# H1FR0.net
KiCad netlist of a schematic drawn in EAGLE
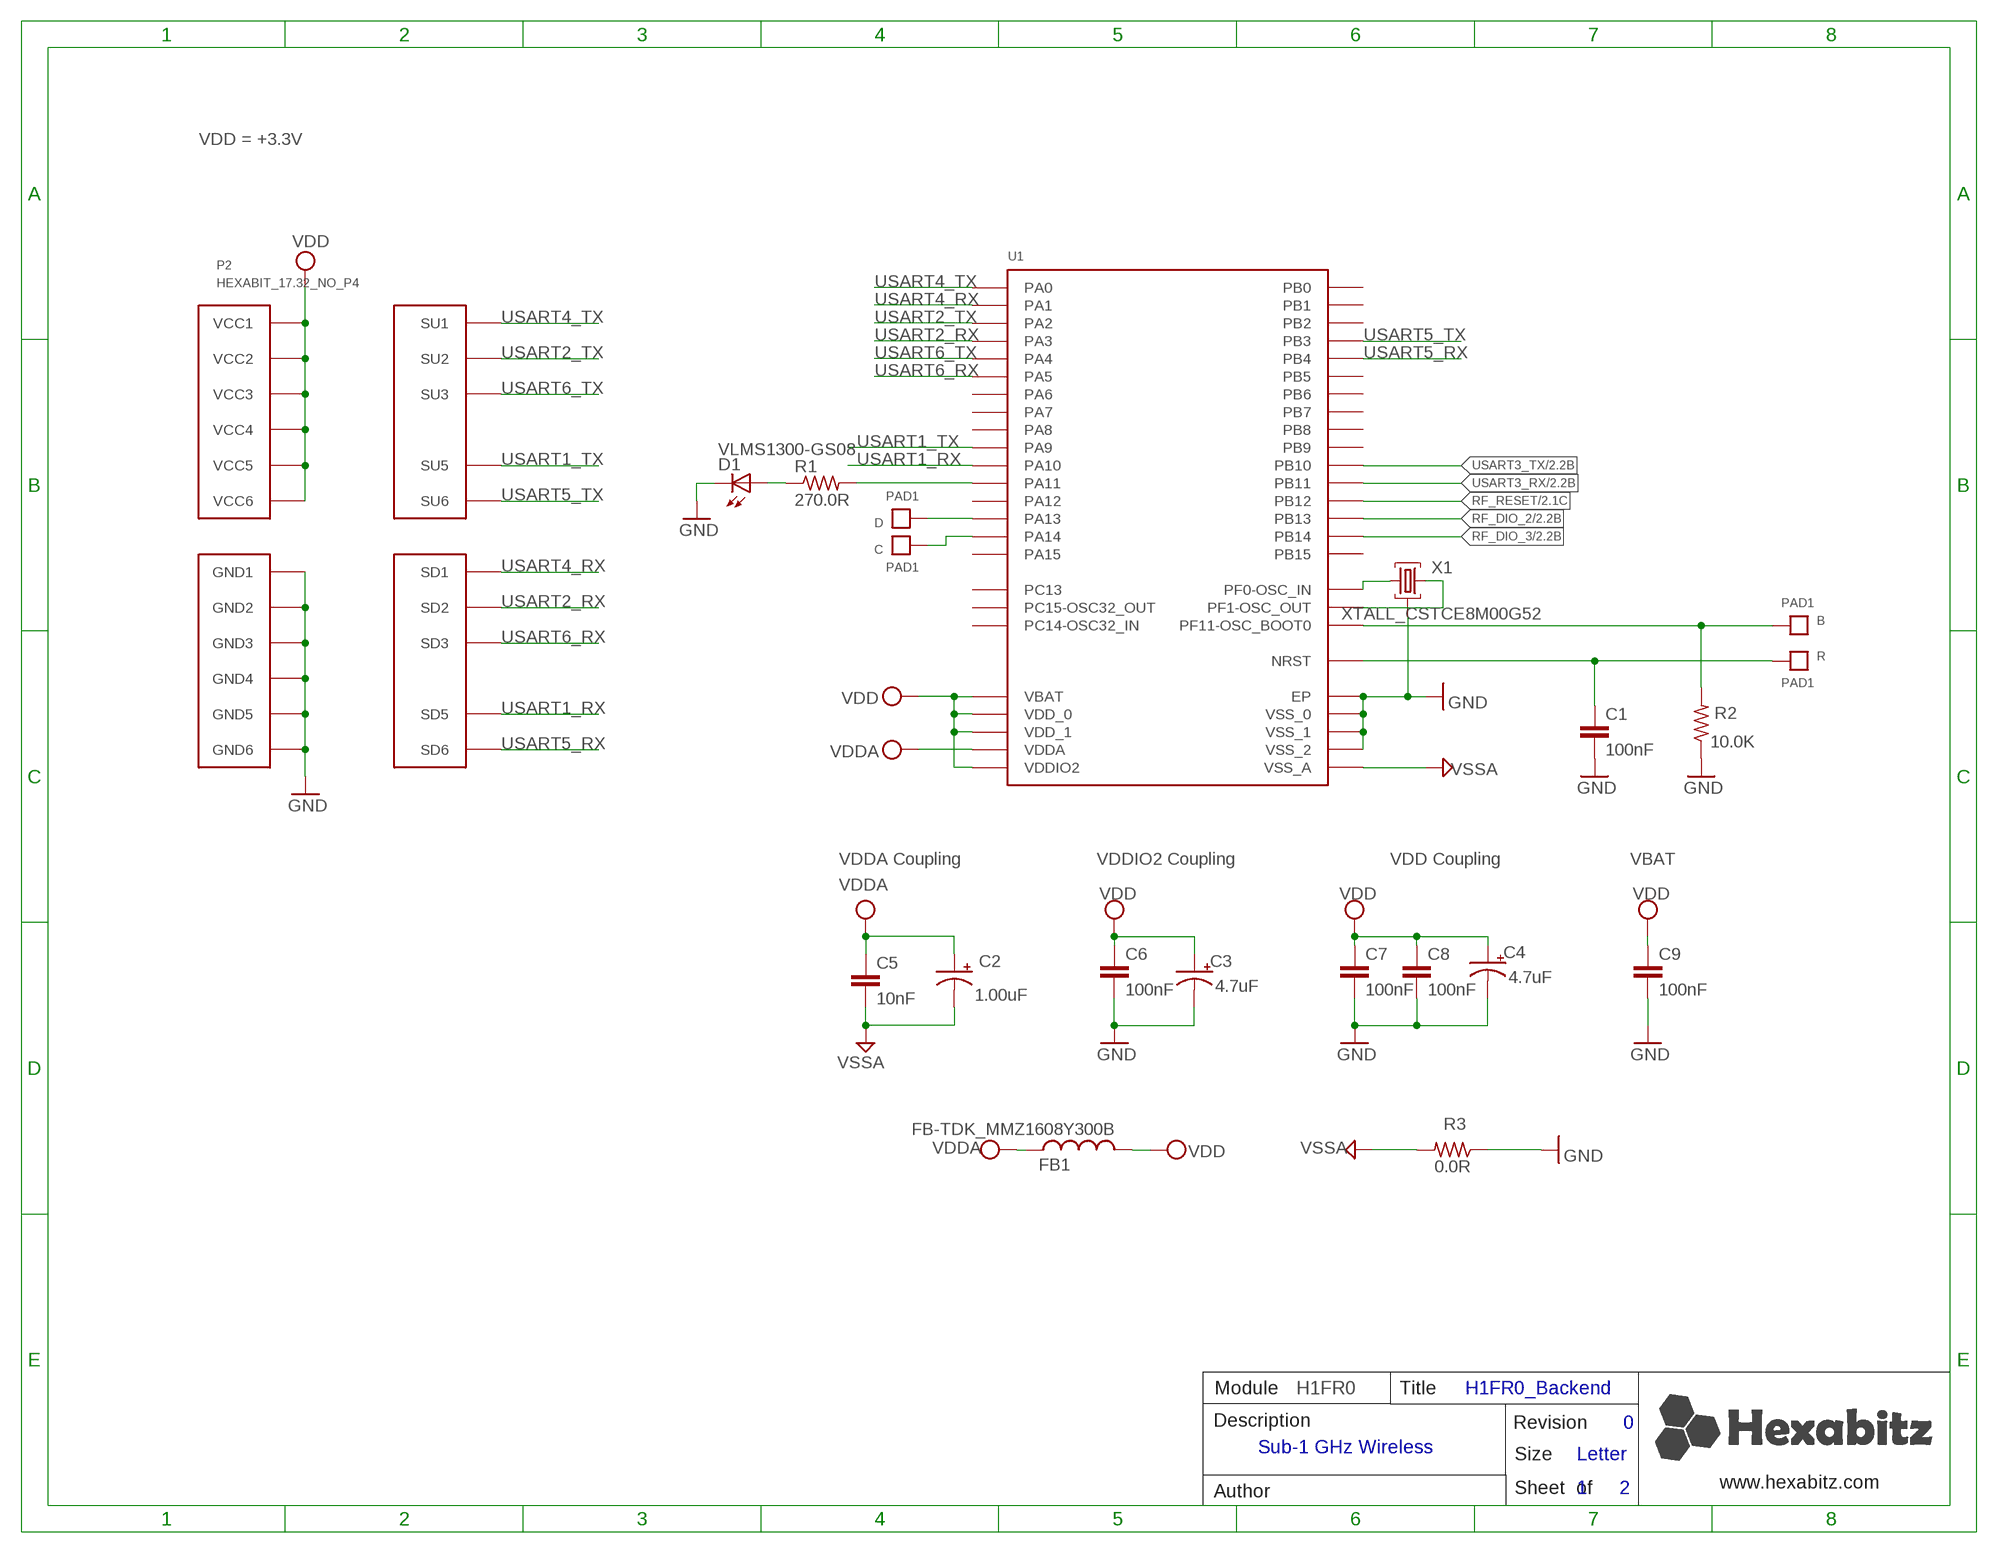
[diagram p0: schematic, sheet 1]
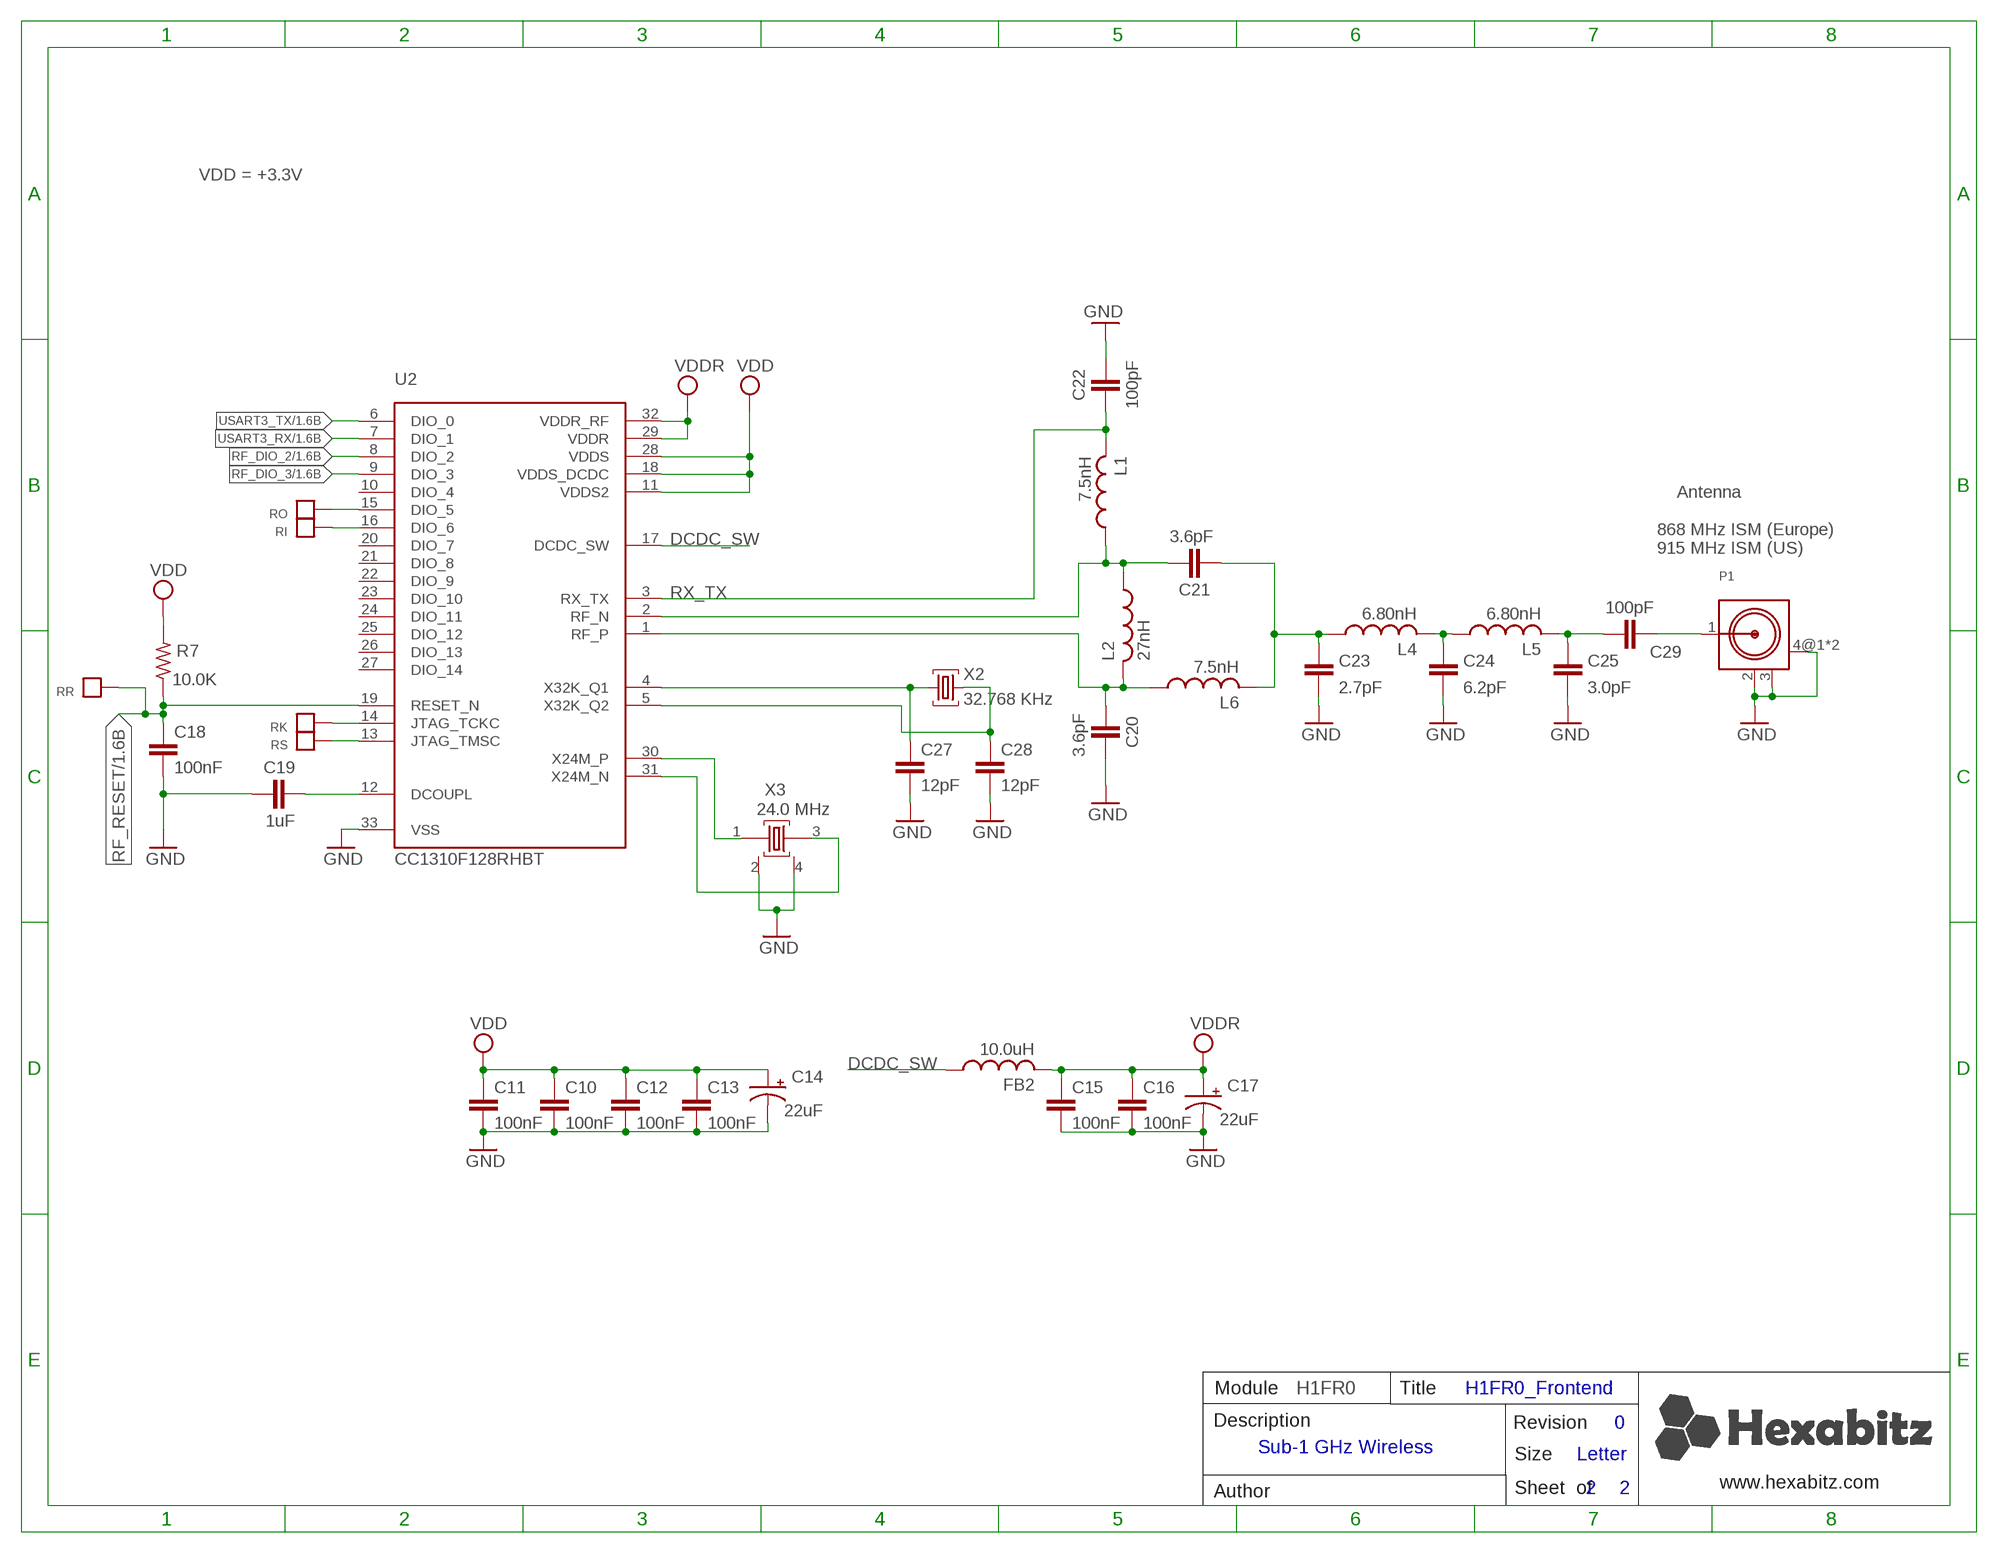
[diagram p1: schematic, sheet 2]

(export (version "E")
  (design (tool "Eeschema 10.0.6"))
  (components
    (comp (ref "C10")
      (value "100nF")
      (footprint "eagle-import:C-0402")
      (fields
        (field (name "MFN") "Murata")
        (field (name "MPN") "GRM155R70J104KA01D")
        (field (name "OCTOPART_URL") "https://octopart.com/grm155r70j104ka01d-murata-17930200")
        (field (name "TOLERANCE") "±10%")
        (field (name "VOLTAGE_RATING") "6.3 V")
      )
      (libsource (lib "eagle-import") (part "C-0402"))
    )
    (comp (ref "C11")
      (value "100nF")
      (footprint "eagle-import:C-0402")
      (fields
        (field (name "MFN") "Murata")
        (field (name "MPN") "GRM155R70J104KA01D")
        (field (name "OCTOPART_URL") "https://octopart.com/grm155r70j104ka01d-murata-17930200")
        (field (name "TOLERANCE") "±10%")
        (field (name "VOLTAGE_RATING") "6.3 V")
      )
      (libsource (lib "eagle-import") (part "C-0402"))
    )
    (comp (ref "C12")
      (value "100nF")
      (footprint "eagle-import:C-0402")
      (fields
        (field (name "MFN") "Murata")
        (field (name "MPN") "GRM155R70J104KA01D")
        (field (name "OCTOPART_URL") "https://octopart.com/grm155r70j104ka01d-murata-17930200")
        (field (name "TOLERANCE") "±10%")
        (field (name "VOLTAGE_RATING") "6.3 V")
      )
      (libsource (lib "eagle-import") (part "C-0402"))
    )
    (comp (ref "C13")
      (value "100nF")
      (footprint "eagle-import:C-0402")
      (fields
        (field (name "MFN") "Murata")
        (field (name "MPN") "GRM155R70J104KA01D")
        (field (name "OCTOPART_URL") "https://octopart.com/grm155r70j104ka01d-murata-17930200")
        (field (name "TOLERANCE") "±10%")
        (field (name "VOLTAGE_RATING") "6.3 V")
      )
      (libsource (lib "eagle-import") (part "C-0402"))
    )
    (comp (ref "C14")
      (value "22uF")
      (footprint "eagle-import:C-0805")
      (fields
        (field (name "CAPACITANCE") "22uF")
        (field (name "MFN") "Yageo")
        (field (name "MPN") "CC0805KKX5R5BB226")
        (field (name "OCTOPART_URL") "https://octopart.com/search?q=CC0805KKX5R5BB226&start=0")
        (field (name "TOLERANCE") "10%")
        (field (name "VOLTAGE_RATING") "6.3V")
      )
      (libsource (lib "eagle-import") (part "C-0805"))
    )
    (comp (ref "C15")
      (value "100nF")
      (footprint "eagle-import:C-0402")
      (fields
        (field (name "MFN") "Murata")
        (field (name "MPN") "GRM155R70J104KA01D")
        (field (name "OCTOPART_URL") "https://octopart.com/grm155r70j104ka01d-murata-17930200")
        (field (name "TOLERANCE") "±10%")
        (field (name "VOLTAGE_RATING") "6.3 V")
      )
      (libsource (lib "eagle-import") (part "C-0402"))
    )
    (comp (ref "C16")
      (value "100nF")
      (footprint "eagle-import:C-0402")
      (fields
        (field (name "MFN") "Murata")
        (field (name "MPN") "GRM155R70J104KA01D")
        (field (name "OCTOPART_URL") "https://octopart.com/grm155r70j104ka01d-murata-17930200")
        (field (name "TOLERANCE") "±10%")
        (field (name "VOLTAGE_RATING") "6.3 V")
      )
      (libsource (lib "eagle-import") (part "C-0402"))
    )
    (comp (ref "C17")
      (value "22uF")
      (footprint "eagle-import:C-0805")
      (fields
        (field (name "CAPACITANCE") "22uF")
        (field (name "MFN") "Yageo")
        (field (name "MPN") "CC0805KKX5R5BB226")
        (field (name "OCTOPART_URL") "https://octopart.com/search?q=CC0805KKX5R5BB226&start=0")
        (field (name "TOLERANCE") "10%")
        (field (name "VOLTAGE_RATING") "6.3V")
      )
      (libsource (lib "eagle-import") (part "C-0805"))
    )
    (comp (ref "C18")
      (value "100nF")
      (footprint "eagle-import:C-0402")
      (fields
        (field (name "MFN") "Murata")
        (field (name "MPN") "GRM155R70J104KA01D")
        (field (name "OCTOPART_URL") "https://octopart.com/grm155r70j104ka01d-murata-17930200")
        (field (name "TOLERANCE") "±10%")
        (field (name "VOLTAGE_RATING") "6.3 V")
      )
      (libsource (lib "eagle-import") (part "C-0402"))
    )
    (comp (ref "C19")
      (value "1uF")
      (footprint "eagle-import:C-0603")
      (fields
        (field (name "CAPACITANCE") "1uF")
        (field (name "MFN") "Murata")
        (field (name "MPN") "GRM188R70J105KA01D")
        (field (name "OCTOPART_URL") "https://octopart.com/grm188r70j105ka01d-murata-197450")
        (field (name "TOLERANCE") "10%")
        (field (name "VOLTAGE_RATING") "6.3V")
      )
      (libsource (lib "eagle-import") (part "C-0603"))
    )
    (comp (ref "C20")
      (value "3.6pF")
      (footprint "eagle-import:C-0402")
      (fields
        (field (name "MFN") "Murata")
        (field (name "MPN") "GRM1555C1H3R6CA01D")
        (field (name "OCTOPART_URL") "https://octopart.com/grm1555c1h3r6ca01d-murata-18814425")
        (field (name "TOLERANCE") "±0.25pF")
        (field (name "VOLTAGE_RATING") "50 V")
      )
      (libsource (lib "eagle-import") (part "C-0402"))
    )
    (comp (ref "C21")
      (value "3.6pF")
      (footprint "eagle-import:C-0402")
      (fields
        (field (name "MFN") "Murata")
        (field (name "MPN") "GRM1555C1H3R6CA01D")
        (field (name "OCTOPART_URL") "https://octopart.com/grm1555c1h3r6ca01d-murata-18814425")
        (field (name "TOLERANCE") "±0.25%")
        (field (name "VOLTAGE_RATING") "50 V")
      )
      (libsource (lib "eagle-import") (part "C-0402"))
    )
    (comp (ref "C22")
      (value "100pF")
      (footprint "eagle-import:C-0402")
      (fields
        (field (name "MFN") "Murata")
        (field (name "MPN") "GRM1555C1H101JA01D")
        (field (name "OCTOPART_URL") "https://octopart.com/grm1555c1h101ja01d-murata-15197512")
        (field (name "TOLERANCE") "±5%")
        (field (name "VOLTAGE_RATING") "50V")
      )
      (libsource (lib "eagle-import") (part "C-0402"))
    )
    (comp (ref "C23")
      (value "2.7pF")
      (footprint "eagle-import:C-0402")
      (fields
        (field (name "MFN") "Murata")
        (field (name "MPN") "GRM1555C1H2R7CA01D")
        (field (name "OCTOPART_URL") "https://octopart.com/search?q=GRM1555C1H2R7CA01D&start=0")
        (field (name "TOLERANCE") "±0.25 pF")
        (field (name "VOLTAGE_RATING") "50 V")
      )
      (libsource (lib "eagle-import") (part "C-0402"))
    )
    (comp (ref "C24")
      (value "6.2pF")
      (footprint "eagle-import:C-0402")
      (fields
        (field (name "MFN") "Murata")
        (field (name "MPN") "GRM1555C1H6R2CA01D")
        (field (name "OCTOPART_URL") "https://octopart.com/search?q=GRM1555C1H6R2CA01D&start=0")
        (field (name "TOLERANCE") "±0.25pF")
        (field (name "VOLTAGE_RATING") "50 V")
      )
      (libsource (lib "eagle-import") (part "C-0402"))
    )
    (comp (ref "C25")
      (value "3.0pF")
      (footprint "eagle-import:C-0402")
      (fields
        (field (name "MFN") "Murata")
        (field (name "MPN") "GRM1555C1H3R0CA01D")
        (field (name "OCTOPART_URL") "https://octopart.com/search?q=GRM1555C1H3R0CA01D&start=0")
        (field (name "TOLERANCE") "±0.25 pF")
        (field (name "VOLTAGE_RATING") "50 V")
      )
      (libsource (lib "eagle-import") (part "C-0402"))
    )
    (comp (ref "C27")
      (value "12pF")
      (footprint "eagle-import:C-0603")
      (fields
        (field (name "CAPACITANCE") "12pF")
        (field (name "MFN") "AVX")
        (field (name "MPN") "06035A120JAT2A")
        (field (name "OCTOPART_URL") "https://octopart.com/06035a120jat2a-avx-194785")
        (field (name "TOLERANCE") "5%")
        (field (name "VOLTAGE_RATING") "50V")
      )
      (libsource (lib "eagle-import") (part "C-0603"))
    )
    (comp (ref "C28")
      (value "12pF")
      (footprint "eagle-import:C-0603")
      (fields
        (field (name "CAPACITANCE") "12pF")
        (field (name "MFN") "AVX")
        (field (name "MPN") "06035A120JAT2A")
        (field (name "OCTOPART_URL") "https://octopart.com/06035a120jat2a-avx-194785")
        (field (name "TOLERANCE") "5%")
        (field (name "VOLTAGE_RATING") "50V")
      )
      (libsource (lib "eagle-import") (part "C-0603"))
    )
    (comp (ref "C29")
      (value "100pF")
      (footprint "eagle-import:C-0402")
      (fields
        (field (name "MFN") "Murata")
        (field (name "MPN") "GRM1555C1H101JA01D")
        (field (name "OCTOPART_URL") "https://octopart.com/grm1555c1h101ja01d-murata-15197512")
        (field (name "TOLERANCE") "±5%")
        (field (name "VOLTAGE_RATING") "50V")
      )
      (libsource (lib "eagle-import") (part "C-0402"))
    )
    (comp (ref "FB2")
      (value "10.0uH")
      (footprint "eagle-import:FB-0805")
      (fields
        (field (name "MFN") "Taiyo Yuden")
        (field (name "MPN") "CKS2125100M-T")
        (field (name "OCTOPART_URL") "http://octopart.com/cks2125100m-t-taiyo+yuden-18605517")
      )
      (libsource (lib "eagle-import") (part "FB-0805"))
    )
    (comp (ref "L1")
      (value "7.5nH")
      (footprint "eagle-import:IND-0402")
      (fields
        (field (name "INDUCTANCE") "7.5nH")
        (field (name "MFN") "Murata")
        (field (name "MPN") "LQG15HS7N5J02D")
        (field (name "OCTOPART_URL") "https://octopart.com/search?q=LQG15HS7N5J02D&start=0")
      )
      (libsource (lib "eagle-import") (part "IND-0402"))
    )
    (comp (ref "L2")
      (value "27nH")
      (footprint "eagle-import:IND-0402")
      (fields
        (field (name "INDUCTANCE") "27nH")
        (field (name "MFN") "Murata")
        (field (name "MPN") "LQG15HS27NJ02D")
        (field (name "OCTOPART_URL") "https://octopart.com/search?q=LQG15HS27NJ02D&start=0")
      )
      (libsource (lib "eagle-import") (part "IND-0402"))
    )
    (comp (ref "L4")
      (value "6.80nH")
      (footprint "eagle-import:IND-0402")
      (fields
        (field (name "INDUCTANCE") "6.80nH")
        (field (name "MFN") "Murata")
        (field (name "MPN") "LQW15AN6N8G00D")
        (field (name "OCTOPART_URL") "https://octopart.com/lqw15an6n8g00d-murata-7896134")
      )
      (libsource (lib "eagle-import") (part "IND-0402"))
    )
    (comp (ref "L5")
      (value "6.80nH")
      (footprint "eagle-import:IND-0402")
      (fields
        (field (name "INDUCTANCE") "6.80nH")
        (field (name "MFN") "Murata")
        (field (name "MPN") "LQW15AN6N8G00D")
        (field (name "OCTOPART_URL") "https://octopart.com/lqw15an6n8g00d-murata-7896134")
      )
      (libsource (lib "eagle-import") (part "IND-0402"))
    )
    (comp (ref "L6")
      (value "7.5nH")
      (footprint "eagle-import:IND-0402")
      (fields
        (field (name "INDUCTANCE") "7.5nH")
        (field (name "MFN") "Murata")
        (field (name "MPN") "LQG15HS7N5J02D")
        (field (name "OCTOPART_URL") "https://octopart.com/search?q=LQG15HS7N5J02D&start=0")
      )
      (libsource (lib "eagle-import") (part "IND-0402"))
    )
    (comp (ref "P1")
      (value "5-1814400-1")
      (footprint "eagle-import:5-1814400-1")
      (libsource (lib "eagle-import") (part "5-1814400-1"))
    )
    (comp (ref "R7")
      (value "10.0K")
      (footprint "eagle-import:R-0603")
      (fields
        (field (name "MFN") "Yageo")
        (field (name "MPN") "RC0603JR-0710KL")
        (field (name "OCTOPART_URL") "https://octopart.com/search?q=RC0603JR-0710KL&start=0")
        (field (name "RESISTANCE") "10.0K Ohm")
        (field (name "TOLERANCE") "5%")
      )
      (libsource (lib "eagle-import") (part "R-0603"))
    )
    (comp (ref "RI")
      (value "PAD4")
      (footprint "eagle-import:PAD4")
      (libsource (lib "eagle-import") (part "PAD4"))
    )
    (comp (ref "RK")
      (value "PAD4")
      (footprint "eagle-import:PAD4")
      (libsource (lib "eagle-import") (part "PAD4"))
    )
    (comp (ref "RO")
      (value "PAD4")
      (footprint "eagle-import:PAD4")
      (libsource (lib "eagle-import") (part "PAD4"))
    )
    (comp (ref "RR")
      (value "PAD4")
      (footprint "eagle-import:PAD4")
      (libsource (lib "eagle-import") (part "PAD4"))
    )
    (comp (ref "RS")
      (value "PAD4")
      (footprint "eagle-import:PAD4")
      (libsource (lib "eagle-import") (part "PAD4"))
    )
    (comp (ref "U2")
      (value "CC1310F128RHBT")
      (footprint "eagle-import:CC1310F128RHBT")
      (libsource (lib "eagle-import") (part "CC1310F128RHBT"))
    )
    (comp (ref "X2")
      (value "32.768 KHz")
      (footprint "eagle-import:XTALL_FC-12M")
      (fields (field (name "MPN") "FC-12M 32.7680KA-A3"))
      (libsource (lib "eagle-import") (part "XTALL_FC-12M"))
    )
    (comp (ref "X3")
      (value "24.0 MHz")
      (footprint "eagle-import:XTALL_TXS-3225-24.0000M")
      (fields (field (name "MPN") "TSX-3225 24.0000MF20G-AC3"))
      (libsource (lib "eagle-import") (part "XTALL_TXS-3225-24.0000M"))
    )
    (comp (ref "B")
      (value "PAD1")
      (footprint "eagle-import:PAD1")
      (libsource (lib "eagle-import") (part "PAD1"))
    )
    (comp (ref "C")
      (value "PAD1")
      (footprint "eagle-import:PAD1")
      (libsource (lib "eagle-import") (part "PAD1"))
    )
    (comp (ref "C1")
      (value "100nF")
      (footprint "eagle-import:C-0603")
      (fields
        (field (name "CAPACITANCE") "100nF")
        (field (name "MFN") "KEMET")
        (field (name "MPN") "C0603C104K8RACTU")
        (field (name "OCTOPART_URL") "https://octopart.com/c0603c104k8ractu-kemet-145075?r=sp&s=9bS9ASSwSEqMCE9KBEQZ0g")
        (field (name "TOLERANCE") "10%")
        (field (name "VOLTAGE_RATING") "10V")
      )
      (libsource (lib "eagle-import") (part "C-0603"))
    )
    (comp (ref "C2")
      (value "1.00uF")
      (footprint "eagle-import:C-0805")
      (fields
        (field (name "CAPACITANCE") "1.00uF")
        (field (name "MFN") "Yageo")
        (field (name "MPN") "CC0805KKX7R7BB105")
        (field (name "OCTOPART_URL") "https://octopart.com/cc0805kkx7r7bb105-yageo-8376555?r=sp&s=YKl1wwtkROau_X5nniH2ig")
        (field (name "TOLERANCE") "10%")
        (field (name "VOLTAGE_RATING") "16V")
      )
      (libsource (lib "eagle-import") (part "C-0805"))
    )
    (comp (ref "C3")
      (value "4.7uF")
      (footprint "eagle-import:C-0805")
      (fields
        (field (name "CAPACITANCE") "4.7uF")
        (field (name "MFN") "Murata")
        (field (name "MPN") "GRM21BC81E475KA12L")
        (field (name "OCTOPART_URL") "https://octopart.com/grm21bc81e475ka12l-murata-10331911?r=sp&s=RY3qZSD8T6mG6TC9CHI5qQ")
        (field (name "TOLERANCE") "10%")
        (field (name "VOLTAGE_RATING") "25V")
      )
      (libsource (lib "eagle-import") (part "C-0805"))
    )
    (comp (ref "C4")
      (value "4.7uF")
      (footprint "eagle-import:C-0805")
      (fields
        (field (name "CAPACITANCE") "4.7uF")
        (field (name "MFN") "Murata")
        (field (name "MPN") "GRM21BC81E475KA12L")
        (field (name "OCTOPART_URL") "https://octopart.com/grm21bc81e475ka12l-murata-10331911?r=sp&s=RY3qZSD8T6mG6TC9CHI5qQ")
        (field (name "TOLERANCE") "10%")
        (field (name "VOLTAGE_RATING") "25V")
      )
      (libsource (lib "eagle-import") (part "C-0805"))
    )
    (comp (ref "C5")
      (value "10nF")
      (footprint "eagle-import:C-0603")
      (fields
        (field (name "CAPACITANCE") "10nF")
        (field (name "MFN") "KEMET")
        (field (name "MPN") "C0603C103K5RACTU")
        (field (name "OCTOPART_URL") "https://octopart.com/c0603c103k5ractu-kemet-133094?r=sp&s=R_iPBxLnSmGqhkU2rIMFpg")
        (field (name "TOLERANCE") "10%")
        (field (name "VOLTAGE_RATING") "50V")
      )
      (libsource (lib "eagle-import") (part "C-0603"))
    )
    (comp (ref "C6")
      (value "100nF")
      (footprint "eagle-import:C-0603")
      (fields
        (field (name "CAPACITANCE") "100nF")
        (field (name "MFN") "KEMET")
        (field (name "MPN") "C0603C104K8RACTU")
        (field (name "OCTOPART_URL") "https://octopart.com/c0603c104k8ractu-kemet-145075?r=sp&s=9bS9ASSwSEqMCE9KBEQZ0g")
        (field (name "TOLERANCE") "10%")
        (field (name "VOLTAGE_RATING") "10V")
      )
      (libsource (lib "eagle-import") (part "C-0603"))
    )
    (comp (ref "C7")
      (value "100nF")
      (footprint "eagle-import:C-0603")
      (fields
        (field (name "CAPACITANCE") "100nF")
        (field (name "MFN") "KEMET")
        (field (name "MPN") "C0603C104K8RACTU")
        (field (name "OCTOPART_URL") "https://octopart.com/c0603c104k8ractu-kemet-145075?r=sp&s=9bS9ASSwSEqMCE9KBEQZ0g")
        (field (name "TOLERANCE") "10%")
        (field (name "VOLTAGE_RATING") "10")
      )
      (libsource (lib "eagle-import") (part "C-0603"))
    )
    (comp (ref "C8")
      (value "100nF")
      (footprint "eagle-import:C-0603")
      (fields
        (field (name "CAPACITANCE") "100nF")
        (field (name "MFN") "KEMET")
        (field (name "MPN") "C0603C104K8RACTU")
        (field (name "OCTOPART_URL") "https://octopart.com/c0603c104k8ractu-kemet-145075?r=sp&s=9bS9ASSwSEqMCE9KBEQZ0g")
        (field (name "TOLERANCE") "10%")
        (field (name "VOLTAGE_RATING") "10V")
      )
      (libsource (lib "eagle-import") (part "C-0603"))
    )
    (comp (ref "C9")
      (value "100nF")
      (footprint "eagle-import:C-0603")
      (fields
        (field (name "CAPACITANCE") "100nF")
        (field (name "MFN") "KEMET")
        (field (name "MPN") "C0603C104K8RACTU")
        (field (name "OCTOPART_URL") "https://octopart.com/c0603c104k8ractu-kemet-145075?r=sp&s=9bS9ASSwSEqMCE9KBEQZ0g")
        (field (name "TOLERANCE") "10V")
        (field (name "VOLTAGE_RATING") "10%")
      )
      (libsource (lib "eagle-import") (part "C-0603"))
    )
    (comp (ref "D")
      (value "PAD1")
      (footprint "eagle-import:PAD1")
      (libsource (lib "eagle-import") (part "PAD1"))
    )
    (comp (ref "D1")
      (value "VLMS1300-GS08")
      (footprint "eagle-import:VLMS1300-GS08")
      (fields
        (field (name "MFN") "Vishay")
        (field (name "MPN") "VLMS1300-GS08")
        (field (name "OCTOPART_URL") "https://octopart.com/vlms1300-gs08-vishay-21709201?r=sp&s=_gcP4_q8T1SC6PJQPTQ9yA")
      )
      (libsource (lib "eagle-import") (part "VLMS1300-GS08"))
    )
    (comp (ref "FB1")
      (value "FB-TDK_MMZ1608Y300B")
      (footprint "eagle-import:FB-TDK_MMZ1608Y300B")
      (fields
        (field (name "MFN") "TDK ")
        (field (name "MPN") "MMZ1608Y300B")
        (field (name "OCTOPART_URL") "https://octopart.com/mmz1608y300b-tdk-368280?r=sp&s=cd9_2ZEqQ9q9UNBuQgHAiA")
      )
      (libsource (lib "eagle-import") (part "FB-TDK_MMZ1608Y300B"))
    )
    (comp (ref "P2")
      (value "HEXABIT_17.32_NO_P4")
      (footprint "eagle-import:HEXABIT_17.32_NO_P4")
      (libsource (lib "eagle-import") (part "HEXABIT_17.32_NO_P4"))
    )
    (comp (ref "R")
      (value "PAD1")
      (footprint "eagle-import:PAD1")
      (libsource (lib "eagle-import") (part "PAD1"))
    )
    (comp (ref "R1")
      (value "270.0R")
      (footprint "eagle-import:R-0603")
      (fields
        (field (name "MFN") "Yageo")
        (field (name "MPN") "RC0603FR-07270RL")
        (field (name "OCTOPART_URL") "https://octopart.com/search?q=RC0603FR-07270RL&start=0")
        (field (name "RESISTANCE") "270.0 Ohm")
        (field (name "TOLERANCE") "1%")
      )
      (libsource (lib "eagle-import") (part "R-0603"))
    )
    (comp (ref "R2")
      (value "10.0K")
      (footprint "eagle-import:R-0603")
      (fields
        (field (name "MFN") "Yageo")
        (field (name "MPN") "RC0603JR-0710KL")
        (field (name "OCTOPART_URL") "https://octopart.com/search?q=RC0603JR-0710KL&start=0")
        (field (name "RESISTANCE") "10.0K Ohm")
        (field (name "TOLERANCE") "5%")
      )
      (libsource (lib "eagle-import") (part "R-0603"))
    )
    (comp (ref "R3")
      (value "0.0R")
      (footprint "eagle-import:R-0603")
      (fields
        (field (name "MFN") "Yageo")
        (field (name "MPN") "RC0603JR-070RL")
        (field (name "OCTOPART_URL") "https://octopart.com/rc0603jr-070rl-yageo-1241539?r=sp&s=X2NteqRjRNWrnx42Y0aliA")
        (field (name "RESISTANCE") "0.0 Ohm")
      )
      (libsource (lib "eagle-import") (part "R-0603"))
    )
    (comp (ref "U1")
      (value "STM32F091CBU6")
      (footprint "eagle-import:STM32F091CBU6")
      (libsource (lib "eagle-import") (part "STM32F091CBU6"))
    )
    (comp (ref "X1")
      (value "XTALL_CSTCE8M00G52")
      (footprint "eagle-import:XTALL_CSTCE8M00G52")
      (fields (field (name "MPN") "CSTCE8M00G52Z-R0"))
      (libsource (lib "eagle-import") (part "XTALL_CSTCE8M00G52"))
    )
  )
  (nets
    (net (code "1") (name "DCDC_SW") (class "Default")
      (node (ref "FB2") (pin "1") (pinfunction "1_1") (pintype "passive"))
      (node (ref "U2") (pin "17") (pinfunction "DCDC_SW_17") (pintype "bidirectional"))
    )
    (net (code "2") (name "GND") (class "Default")
      (node (ref "C1") (pin "2") (pinfunction "2_2") (pintype "passive"))
      (node (ref "C10") (pin "2") (pinfunction "2_2") (pintype "passive"))
      (node (ref "C11") (pin "2") (pinfunction "2_2") (pintype "passive"))
      (node (ref "C12") (pin "2") (pinfunction "2_2") (pintype "passive"))
      (node (ref "C13") (pin "2") (pinfunction "2_2") (pintype "passive"))
      (node (ref "C14") (pin "2") (pinfunction "-_2") (pintype "passive"))
      (node (ref "C15") (pin "2") (pinfunction "2_2") (pintype "passive"))
      (node (ref "C16") (pin "2") (pinfunction "2_2") (pintype "passive"))
      (node (ref "C17") (pin "2") (pinfunction "-_2") (pintype "passive"))
      (node (ref "C18") (pin "2") (pinfunction "2_2") (pintype "passive"))
      (node (ref "C19") (pin "1") (pinfunction "1_1") (pintype "passive"))
      (node (ref "C20") (pin "2") (pinfunction "2_2") (pintype "passive"))
      (node (ref "C22") (pin "2") (pinfunction "2_2") (pintype "passive"))
      (node (ref "C23") (pin "1") (pinfunction "1_1") (pintype "passive"))
      (node (ref "C24") (pin "1") (pinfunction "1_1") (pintype "passive"))
      (node (ref "C25") (pin "1") (pinfunction "1_1") (pintype "passive"))
      (node (ref "C27") (pin "2") (pinfunction "2_2") (pintype "passive"))
      (node (ref "C28") (pin "2") (pinfunction "2_2") (pintype "passive"))
      (node (ref "C3") (pin "2") (pinfunction "-_2") (pintype "passive"))
      (node (ref "C4") (pin "2") (pinfunction "-_2") (pintype "passive"))
      (node (ref "C6") (pin "2") (pinfunction "2_2") (pintype "passive"))
      (node (ref "C7") (pin "2") (pinfunction "2_2") (pintype "passive"))
      (node (ref "C8") (pin "2") (pinfunction "2_2") (pintype "passive"))
      (node (ref "C9") (pin "2") (pinfunction "2_2") (pintype "passive"))
      (node (ref "D1") (pin "C") (pinfunction "C_C") (pintype "passive"))
      (node (ref "P1") (pin "2") (pinfunction "2_2") (pintype "bidirectional"))
      (node (ref "P1") (pin "3") (pinfunction "3_3") (pintype "bidirectional"))
      (node (ref "P1") (pin "4@1") (pinfunction "4_4@1") (pintype "bidirectional"))
      (node (ref "P1") (pin "4@2") (pinfunction "4_4@2") (pintype "bidirectional"))
      (node (ref "P2") (pin "10") (pinfunction "GND4_10") (pintype "power_in"))
      (node (ref "P2") (pin "11") (pinfunction "GND5_11") (pintype "power_in"))
      (node (ref "P2") (pin "12") (pinfunction "GND6_12") (pintype "power_in"))
      (node (ref "P2") (pin "7") (pinfunction "GND1_7") (pintype "power_in"))
      (node (ref "P2") (pin "8") (pinfunction "GND2_8") (pintype "power_in"))
      (node (ref "P2") (pin "9") (pinfunction "GND3_9") (pintype "power_in"))
      (node (ref "R2") (pin "1") (pinfunction "1_1") (pintype "passive"))
      (node (ref "R3") (pin "1") (pinfunction "1_1") (pintype "passive"))
      (node (ref "U1") (pin "EP") (pinfunction "EP_EP") (pintype "power_in"))
      (node (ref "U1") (pin "P$23") (pinfunction "VSS_0_P$23") (pintype "power_in"))
      (node (ref "U1") (pin "P$35") (pinfunction "VSS_1_P$35") (pintype "power_in"))
      (node (ref "U1") (pin "P$47") (pinfunction "VSS_2_P$47") (pintype "power_in"))
      (node (ref "U2") (pin "33") (pinfunction "VSS_33") (pintype "bidirectional"))
      (node (ref "X1") (pin "P$2") (pinfunction "2_P$2") (pintype "passive"))
      (node (ref "X3") (pin "2") (pinfunction "2_2") (pintype "passive"))
      (node (ref "X3") (pin "4") (pinfunction "4_4") (pintype "passive"))
    )
    (net (code "3") (name "Net-(C21-Pad1)") (class "Default")
      (node (ref "C21") (pin "1") (pinfunction "1_1") (pintype "passive"))
      (node (ref "C23") (pin "2") (pinfunction "2_2") (pintype "passive"))
      (node (ref "L4") (pin "1") (pinfunction "1_1") (pintype "passive"))
      (node (ref "L6") (pin "2") (pinfunction "2_2") (pintype "passive"))
    )
    (net (code "4") (name "Net-(C24-Pad2)") (class "Default")
      (node (ref "C24") (pin "2") (pinfunction "2_2") (pintype "passive"))
      (node (ref "L4") (pin "2") (pinfunction "2_2") (pintype "passive"))
      (node (ref "L5") (pin "1") (pinfunction "1_1") (pintype "passive"))
    )
    (net (code "5") (name "Net-(C25-Pad2)") (class "Default")
      (node (ref "C25") (pin "2") (pinfunction "2_2") (pintype "passive"))
      (node (ref "C29") (pin "2") (pinfunction "2_2") (pintype "passive"))
      (node (ref "L5") (pin "2") (pinfunction "2_2") (pintype "passive"))
    )
    (net (code "6") (name "Net-(C29-Pad1)") (class "Default")
      (node (ref "C29") (pin "1") (pinfunction "1_1") (pintype "passive"))
      (node (ref "P1") (pin "1") (pinfunction "1_1") (pintype "bidirectional"))
    )
    (net (code "7") (name "Net-(D1-PadA)") (class "Default")
      (node (ref "D1") (pin "A") (pinfunction "A_A") (pintype "passive"))
      (node (ref "R1") (pin "1") (pinfunction "1_1") (pintype "passive"))
    )
    (net (code "8") (name "Net-(U1-NRST)") (class "Default")
      (node (ref "C1") (pin "1") (pinfunction "1_1") (pintype "passive"))
      (node (ref "R") (pin "P$1") (pinfunction "P$1_P$1") (pintype "passive"))
      (node (ref "R") (pin "P$2") (pinfunction "P$1_P$2") (pintype "passive"))
      (node (ref "U1") (pin "P$7") (pinfunction "NRST_P$7") (pintype "passive"))
    )
    (net (code "9") (name "Net-(U1-PA11)") (class "Default")
      (node (ref "R1") (pin "2") (pinfunction "2_2") (pintype "passive"))
      (node (ref "U1") (pin "P$32") (pinfunction "PA11_P$32") (pintype "bidirectional"))
    )
    (net (code "10") (name "Net-(U1-PA13)") (class "Default")
      (node (ref "D") (pin "P$1") (pinfunction "P$1_P$1") (pintype "passive"))
      (node (ref "D") (pin "P$2") (pinfunction "P$1_P$2") (pintype "passive"))
      (node (ref "U1") (pin "P$34") (pinfunction "PA13_P$34") (pintype "bidirectional"))
    )
    (net (code "11") (name "Net-(U1-PA14)") (class "Default")
      (node (ref "C") (pin "P$1") (pinfunction "P$1_P$1") (pintype "passive"))
      (node (ref "C") (pin "P$2") (pinfunction "P$1_P$2") (pintype "passive"))
      (node (ref "U1") (pin "P$37") (pinfunction "PA14_P$37") (pintype "bidirectional"))
    )
    (net (code "12") (name "Net-(U1-PF0-OSC_IN)") (class "Default")
      (node (ref "U1") (pin "P$5") (pinfunction "PF0-OSC_IN_P$5") (pintype "bidirectional"))
      (node (ref "X1") (pin "P$1") (pinfunction "1_P$1") (pintype "passive"))
    )
    (net (code "13") (name "Net-(U1-PF1-OSC_OUT)") (class "Default")
      (node (ref "U1") (pin "P$6") (pinfunction "PF1-OSC_OUT_P$6") (pintype "bidirectional"))
      (node (ref "X1") (pin "P$3") (pinfunction "3_P$3") (pintype "passive"))
    )
    (net (code "14") (name "Net-(U1-PF11-OSC_BOOT0)") (class "Default")
      (node (ref "B") (pin "P$1") (pinfunction "P$1_P$1") (pintype "passive"))
      (node (ref "B") (pin "P$2") (pinfunction "P$1_P$2") (pintype "passive"))
      (node (ref "R2") (pin "2") (pinfunction "2_2") (pintype "passive"))
      (node (ref "U1") (pin "P$44") (pinfunction "PF11-OSC_BOOT0_P$44") (pintype "bidirectional"))
    )
    (net (code "15") (name "Net-(U2-DCOUPL)") (class "Default")
      (node (ref "C19") (pin "2") (pinfunction "2_2") (pintype "passive"))
      (node (ref "U2") (pin "12") (pinfunction "DCOUPL_12") (pintype "bidirectional"))
    )
    (net (code "16") (name "Net-(U2-DIO_5)") (class "Default")
      (node (ref "RO") (pin "P$1") (pinfunction "P$1_P$1") (pintype "passive"))
      (node (ref "U2") (pin "15") (pinfunction "DIO_5_15") (pintype "bidirectional"))
    )
    (net (code "17") (name "Net-(U2-DIO_6)") (class "Default")
      (node (ref "RI") (pin "P$1") (pinfunction "P$1_P$1") (pintype "passive"))
      (node (ref "U2") (pin "16") (pinfunction "DIO_6_16") (pintype "bidirectional"))
    )
    (net (code "18") (name "Net-(U2-JTAG_TCKC)") (class "Default")
      (node (ref "RK") (pin "P$1") (pinfunction "P$1_P$1") (pintype "passive"))
      (node (ref "U2") (pin "14") (pinfunction "JTAG_TCKC_14") (pintype "bidirectional"))
    )
    (net (code "19") (name "Net-(U2-JTAG_TMSC)") (class "Default")
      (node (ref "RS") (pin "P$1") (pinfunction "P$1_P$1") (pintype "passive"))
      (node (ref "U2") (pin "13") (pinfunction "JTAG_TMSC_13") (pintype "bidirectional"))
    )
    (net (code "20") (name "Net-(U2-RF_N)") (class "Default")
      (node (ref "C21") (pin "2") (pinfunction "2_2") (pintype "passive"))
      (node (ref "L1") (pin "1") (pinfunction "1_1") (pintype "passive"))
      (node (ref "L2") (pin "1") (pinfunction "1_1") (pintype "passive"))
      (node (ref "U2") (pin "2") (pinfunction "RF_N_2") (pintype "bidirectional"))
    )
    (net (code "21") (name "Net-(U2-RF_P)") (class "Default")
      (node (ref "C20") (pin "1") (pinfunction "1_1") (pintype "passive"))
      (node (ref "L2") (pin "2") (pinfunction "2_2") (pintype "passive"))
      (node (ref "L6") (pin "1") (pinfunction "1_1") (pintype "passive"))
      (node (ref "U2") (pin "1") (pinfunction "RF_P_1") (pintype "bidirectional"))
    )
    (net (code "22") (name "Net-(U2-X24M_N)") (class "Default")
      (node (ref "U2") (pin "31") (pinfunction "X24M_N_31") (pintype "bidirectional"))
      (node (ref "X3") (pin "3") (pinfunction "3_3") (pintype "passive"))
    )
    (net (code "23") (name "Net-(U2-X24M_P)") (class "Default")
      (node (ref "U2") (pin "30") (pinfunction "X24M_P_30") (pintype "bidirectional"))
      (node (ref "X3") (pin "1") (pinfunction "1_1") (pintype "passive"))
    )
    (net (code "24") (name "Net-(U2-X32K_Q1)") (class "Default")
      (node (ref "C27") (pin "1") (pinfunction "1_1") (pintype "passive"))
      (node (ref "U2") (pin "4") (pinfunction "X32K_Q1_4") (pintype "bidirectional"))
      (node (ref "X2") (pin "P$2") (pinfunction "2_P$2") (pintype "passive"))
    )
    (net (code "25") (name "Net-(U2-X32K_Q2)") (class "Default")
      (node (ref "C28") (pin "1") (pinfunction "1_1") (pintype "passive"))
      (node (ref "U2") (pin "5") (pinfunction "X32K_Q2_5") (pintype "bidirectional"))
      (node (ref "X2") (pin "P$1") (pinfunction "1_P$1") (pintype "passive"))
    )
    (net (code "26") (name "RF_DIO_2") (class "Default")
      (node (ref "U1") (pin "P$26") (pinfunction "PB13_P$26") (pintype "bidirectional"))
      (node (ref "U2") (pin "8") (pinfunction "DIO_2_8") (pintype "bidirectional"))
    )
    (net (code "27") (name "RF_DIO_3") (class "Default")
      (node (ref "U1") (pin "P$27") (pinfunction "PB14_P$27") (pintype "bidirectional"))
      (node (ref "U2") (pin "9") (pinfunction "DIO_3_9") (pintype "bidirectional"))
    )
    (net (code "28") (name "RF_RESET") (class "Default")
      (node (ref "C18") (pin "1") (pinfunction "1_1") (pintype "passive"))
      (node (ref "R7") (pin "1") (pinfunction "1_1") (pintype "passive"))
      (node (ref "RR") (pin "P$1") (pinfunction "P$1_P$1") (pintype "passive"))
      (node (ref "U1") (pin "P$25") (pinfunction "PB12_P$25") (pintype "bidirectional"))
      (node (ref "U2") (pin "19") (pinfunction "RESET_N_19") (pintype "bidirectional"))
    )
    (net (code "29") (name "RX_TX") (class "Default")
      (node (ref "C22") (pin "1") (pinfunction "1_1") (pintype "passive"))
      (node (ref "L1") (pin "2") (pinfunction "2_2") (pintype "passive"))
      (node (ref "U2") (pin "3") (pinfunction "RX_TX_3") (pintype "bidirectional"))
    )
    (net (code "30") (name "USART1_RX") (class "Default")
      (node (ref "P2") (pin "23") (pinfunction "SD5_23") (pintype "bidirectional"))
      (node (ref "U1") (pin "P$31") (pinfunction "PA10_P$31") (pintype "bidirectional"))
    )
    (net (code "31") (name "USART1_TX") (class "Default")
      (node (ref "P2") (pin "17") (pinfunction "SU5_17") (pintype "bidirectional"))
      (node (ref "U1") (pin "P$30") (pinfunction "PA9_P$30") (pintype "bidirectional"))
    )
    (net (code "32") (name "USART2_RX") (class "Default")
      (node (ref "P2") (pin "20") (pinfunction "SD2_20") (pintype "bidirectional"))
      (node (ref "U1") (pin "P$13") (pinfunction "PA3_P$13") (pintype "bidirectional"))
    )
    (net (code "33") (name "USART2_TX") (class "Default")
      (node (ref "P2") (pin "14") (pinfunction "SU2_14") (pintype "bidirectional"))
      (node (ref "U1") (pin "P$12") (pinfunction "PA2_P$12") (pintype "bidirectional"))
    )
    (net (code "34") (name "USART3_RX") (class "Default")
      (node (ref "U1") (pin "P$22") (pinfunction "PB11_P$22") (pintype "bidirectional"))
      (node (ref "U2") (pin "7") (pinfunction "DIO_1_7") (pintype "bidirectional"))
    )
    (net (code "35") (name "USART3_TX") (class "Default")
      (node (ref "U1") (pin "P$21") (pinfunction "PB10_P$21") (pintype "bidirectional"))
      (node (ref "U2") (pin "6") (pinfunction "DIO_0_6") (pintype "bidirectional"))
    )
    (net (code "36") (name "USART4_RX") (class "Default")
      (node (ref "P2") (pin "19") (pinfunction "SD1_19") (pintype "bidirectional"))
      (node (ref "U1") (pin "P$11") (pinfunction "PA1_P$11") (pintype "bidirectional"))
    )
    (net (code "37") (name "USART4_TX") (class "Default")
      (node (ref "P2") (pin "13") (pinfunction "SU1_13") (pintype "bidirectional"))
      (node (ref "U1") (pin "P$10") (pinfunction "PA0_P$10") (pintype "bidirectional"))
    )
    (net (code "38") (name "USART5_RX") (class "Default")
      (node (ref "P2") (pin "25") (pinfunction "SD6_25") (pintype "bidirectional"))
      (node (ref "U1") (pin "P$40") (pinfunction "PB4_P$40") (pintype "bidirectional"))
    )
    (net (code "39") (name "USART5_TX") (class "Default")
      (node (ref "P2") (pin "18") (pinfunction "SU6_18") (pintype "bidirectional"))
      (node (ref "U1") (pin "P$39") (pinfunction "PB3_P$39") (pintype "bidirectional"))
    )
    (net (code "40") (name "USART6_RX") (class "Default")
      (node (ref "P2") (pin "21") (pinfunction "SD3_21") (pintype "bidirectional"))
      (node (ref "U1") (pin "P$15") (pinfunction "PA5_P$15") (pintype "bidirectional"))
    )
    (net (code "41") (name "USART6_TX") (class "Default")
      (node (ref "P2") (pin "15") (pinfunction "SU3_15") (pintype "bidirectional"))
      (node (ref "U1") (pin "P$14") (pinfunction "PA4_P$14") (pintype "bidirectional"))
    )
    (net (code "42") (name "VDD") (class "Default")
      (node (ref "C10") (pin "1") (pinfunction "1_1") (pintype "passive"))
      (node (ref "C11") (pin "1") (pinfunction "1_1") (pintype "passive"))
      (node (ref "C12") (pin "1") (pinfunction "1_1") (pintype "passive"))
      (node (ref "C13") (pin "1") (pinfunction "1_1") (pintype "passive"))
      (node (ref "C14") (pin "1") (pinfunction "+_1") (pintype "passive"))
      (node (ref "C3") (pin "1") (pinfunction "+_1") (pintype "passive"))
      (node (ref "C4") (pin "1") (pinfunction "+_1") (pintype "passive"))
      (node (ref "C6") (pin "1") (pinfunction "1_1") (pintype "passive"))
      (node (ref "C7") (pin "1") (pinfunction "1_1") (pintype "passive"))
      (node (ref "C8") (pin "1") (pinfunction "1_1") (pintype "passive"))
      (node (ref "C9") (pin "1") (pinfunction "1_1") (pintype "passive"))
      (node (ref "FB1") (pin "2") (pinfunction "2_2") (pintype "passive"))
      (node (ref "P2") (pin "1") (pinfunction "VCC1_1") (pintype "power_in"))
      (node (ref "P2") (pin "2") (pinfunction "VCC2_2") (pintype "power_in"))
      (node (ref "P2") (pin "3") (pinfunction "VCC3_3") (pintype "power_in"))
      (node (ref "P2") (pin "4") (pinfunction "VCC4_4") (pintype "power_in"))
      (node (ref "P2") (pin "5") (pinfunction "VCC5_5") (pintype "power_in"))
      (node (ref "P2") (pin "6") (pinfunction "VCC6_6") (pintype "power_in"))
      (node (ref "R7") (pin "2") (pinfunction "2_2") (pintype "passive"))
      (node (ref "U1") (pin "P$1") (pinfunction "VBAT_P$1") (pintype "power_in"))
      (node (ref "U1") (pin "P$24") (pinfunction "VDD_0_P$24") (pintype "power_in"))
      (node (ref "U1") (pin "P$36") (pinfunction "VDDIO2_P$36") (pintype "power_in"))
      (node (ref "U1") (pin "P$48") (pinfunction "VDD_1_P$48") (pintype "power_in"))
      (node (ref "U2") (pin "11") (pinfunction "VDDS2_11") (pintype "bidirectional"))
      (node (ref "U2") (pin "18") (pinfunction "VDDS_DCDC_18") (pintype "bidirectional"))
      (node (ref "U2") (pin "28") (pinfunction "VDDS_28") (pintype "bidirectional"))
    )
    (net (code "43") (name "VDDA") (class "Default")
      (node (ref "C2") (pin "1") (pinfunction "+_1") (pintype "passive"))
      (node (ref "C5") (pin "1") (pinfunction "1_1") (pintype "passive"))
      (node (ref "FB1") (pin "1") (pinfunction "1_1") (pintype "passive"))
      (node (ref "U1") (pin "P$9") (pinfunction "VDDA_P$9") (pintype "power_in"))
    )
    (net (code "44") (name "VPP") (class "Default")
      (node (ref "C15") (pin "1") (pinfunction "1_1") (pintype "passive"))
      (node (ref "C16") (pin "1") (pinfunction "1_1") (pintype "passive"))
      (node (ref "C17") (pin "1") (pinfunction "+_1") (pintype "passive"))
      (node (ref "FB2") (pin "2") (pinfunction "2_2") (pintype "passive"))
      (node (ref "U2") (pin "29") (pinfunction "VDDR_29") (pintype "bidirectional"))
      (node (ref "U2") (pin "32") (pinfunction "VDDR_RF_32") (pintype "bidirectional"))
    )
    (net (code "45") (name "VSSA") (class "Default")
      (node (ref "C2") (pin "2") (pinfunction "-_2") (pintype "passive"))
      (node (ref "C5") (pin "2") (pinfunction "2_2") (pintype "passive"))
      (node (ref "R3") (pin "2") (pinfunction "2_2") (pintype "passive"))
      (node (ref "U1") (pin "P$8") (pinfunction "VSS_A_P$8") (pintype "power_in"))
    )
    (net (code "46") (name "unconnected-(U1-PA6-PadP$16)") (class "Default")
      (node (ref "U1") (pin "P$16") (pinfunction "PA6_P$16") (pintype "bidirectional"))
    )
    (net (code "47") (name "unconnected-(U1-PA7-PadP$17)") (class "Default")
      (node (ref "U1") (pin "P$17") (pinfunction "PA7_P$17") (pintype "bidirectional"))
    )
    (net (code "48") (name "unconnected-(U1-PA8-PadP$29)") (class "Default")
      (node (ref "U1") (pin "P$29") (pinfunction "PA8_P$29") (pintype "bidirectional"))
    )
    (net (code "49") (name "unconnected-(U1-PA12-PadP$33)") (class "Default")
      (node (ref "U1") (pin "P$33") (pinfunction "PA12_P$33") (pintype "bidirectional"))
    )
    (net (code "50") (name "unconnected-(U1-PA15-PadP$38)") (class "Default")
      (node (ref "U1") (pin "P$38") (pinfunction "PA15_P$38") (pintype "bidirectional"))
    )
    (net (code "51") (name "unconnected-(U1-PB0-PadP$18)") (class "Default")
      (node (ref "U1") (pin "P$18") (pinfunction "PB0_P$18") (pintype "bidirectional"))
    )
    (net (code "52") (name "unconnected-(U1-PB1-PadP$19)") (class "Default")
      (node (ref "U1") (pin "P$19") (pinfunction "PB1_P$19") (pintype "bidirectional"))
    )
    (net (code "53") (name "unconnected-(U1-PB2-PadP$20)") (class "Default")
      (node (ref "U1") (pin "P$20") (pinfunction "PB2_P$20") (pintype "bidirectional"))
    )
    (net (code "54") (name "unconnected-(U1-PB5-PadP$41)") (class "Default")
      (node (ref "U1") (pin "P$41") (pinfunction "PB5_P$41") (pintype "bidirectional"))
    )
    (net (code "55") (name "unconnected-(U1-PB6-PadP$42)") (class "Default")
      (node (ref "U1") (pin "P$42") (pinfunction "PB6_P$42") (pintype "bidirectional"))
    )
    (net (code "56") (name "unconnected-(U1-PB7-PadP$43)") (class "Default")
      (node (ref "U1") (pin "P$43") (pinfunction "PB7_P$43") (pintype "bidirectional"))
    )
    (net (code "57") (name "unconnected-(U1-PB8-PadP$45)") (class "Default")
      (node (ref "U1") (pin "P$45") (pinfunction "PB8_P$45") (pintype "bidirectional"))
    )
    (net (code "58") (name "unconnected-(U1-PB9-PadP$46)") (class "Default")
      (node (ref "U1") (pin "P$46") (pinfunction "PB9_P$46") (pintype "bidirectional"))
    )
    (net (code "59") (name "unconnected-(U1-PB15-PadP$28)") (class "Default")
      (node (ref "U1") (pin "P$28") (pinfunction "PB15_P$28") (pintype "bidirectional"))
    )
    (net (code "60") (name "unconnected-(U1-PC13-PadP$2)") (class "Default")
      (node (ref "U1") (pin "P$2") (pinfunction "PC13_P$2") (pintype "bidirectional"))
    )
    (net (code "61") (name "unconnected-(U1-PC14-OSC32_IN-PadP$3)") (class "Default")
      (node (ref "U1") (pin "P$3") (pinfunction "PC14-OSC32_IN_P$3") (pintype "bidirectional"))
    )
    (net (code "62") (name "unconnected-(U1-PC15-OSC32_OUT-PadP$4)") (class "Default")
      (node (ref "U1") (pin "P$4") (pinfunction "PC15-OSC32_OUT_P$4") (pintype "bidirectional"))
    )
    (net (code "63") (name "unconnected-(U2-DIO_4-Pad10)") (class "Default")
      (node (ref "U2") (pin "10") (pinfunction "DIO_4_10") (pintype "bidirectional"))
    )
    (net (code "64") (name "unconnected-(U2-DIO_7-Pad20)") (class "Default")
      (node (ref "U2") (pin "20") (pinfunction "DIO_7_20") (pintype "bidirectional"))
    )
    (net (code "65") (name "unconnected-(U2-DIO_8-Pad21)") (class "Default")
      (node (ref "U2") (pin "21") (pinfunction "DIO_8_21") (pintype "bidirectional"))
    )
    (net (code "66") (name "unconnected-(U2-DIO_9-Pad22)") (class "Default")
      (node (ref "U2") (pin "22") (pinfunction "DIO_9_22") (pintype "bidirectional"))
    )
    (net (code "67") (name "unconnected-(U2-DIO_10-Pad23)") (class "Default")
      (node (ref "U2") (pin "23") (pinfunction "DIO_10_23") (pintype "bidirectional"))
    )
    (net (code "68") (name "unconnected-(U2-DIO_11-Pad24)") (class "Default")
      (node (ref "U2") (pin "24") (pinfunction "DIO_11_24") (pintype "bidirectional"))
    )
    (net (code "69") (name "unconnected-(U2-DIO_12-Pad25)") (class "Default")
      (node (ref "U2") (pin "25") (pinfunction "DIO_12_25") (pintype "bidirectional"))
    )
    (net (code "70") (name "unconnected-(U2-DIO_13-Pad26)") (class "Default")
      (node (ref "U2") (pin "26") (pinfunction "DIO_13_26") (pintype "bidirectional"))
    )
    (net (code "71") (name "unconnected-(U2-DIO_14-Pad27)") (class "Default")
      (node (ref "U2") (pin "27") (pinfunction "DIO_14_27") (pintype "bidirectional"))
    )
  )
)
